# LoRasPi_02.net
KiCad netlist of a schematic drawn in Altium Designer
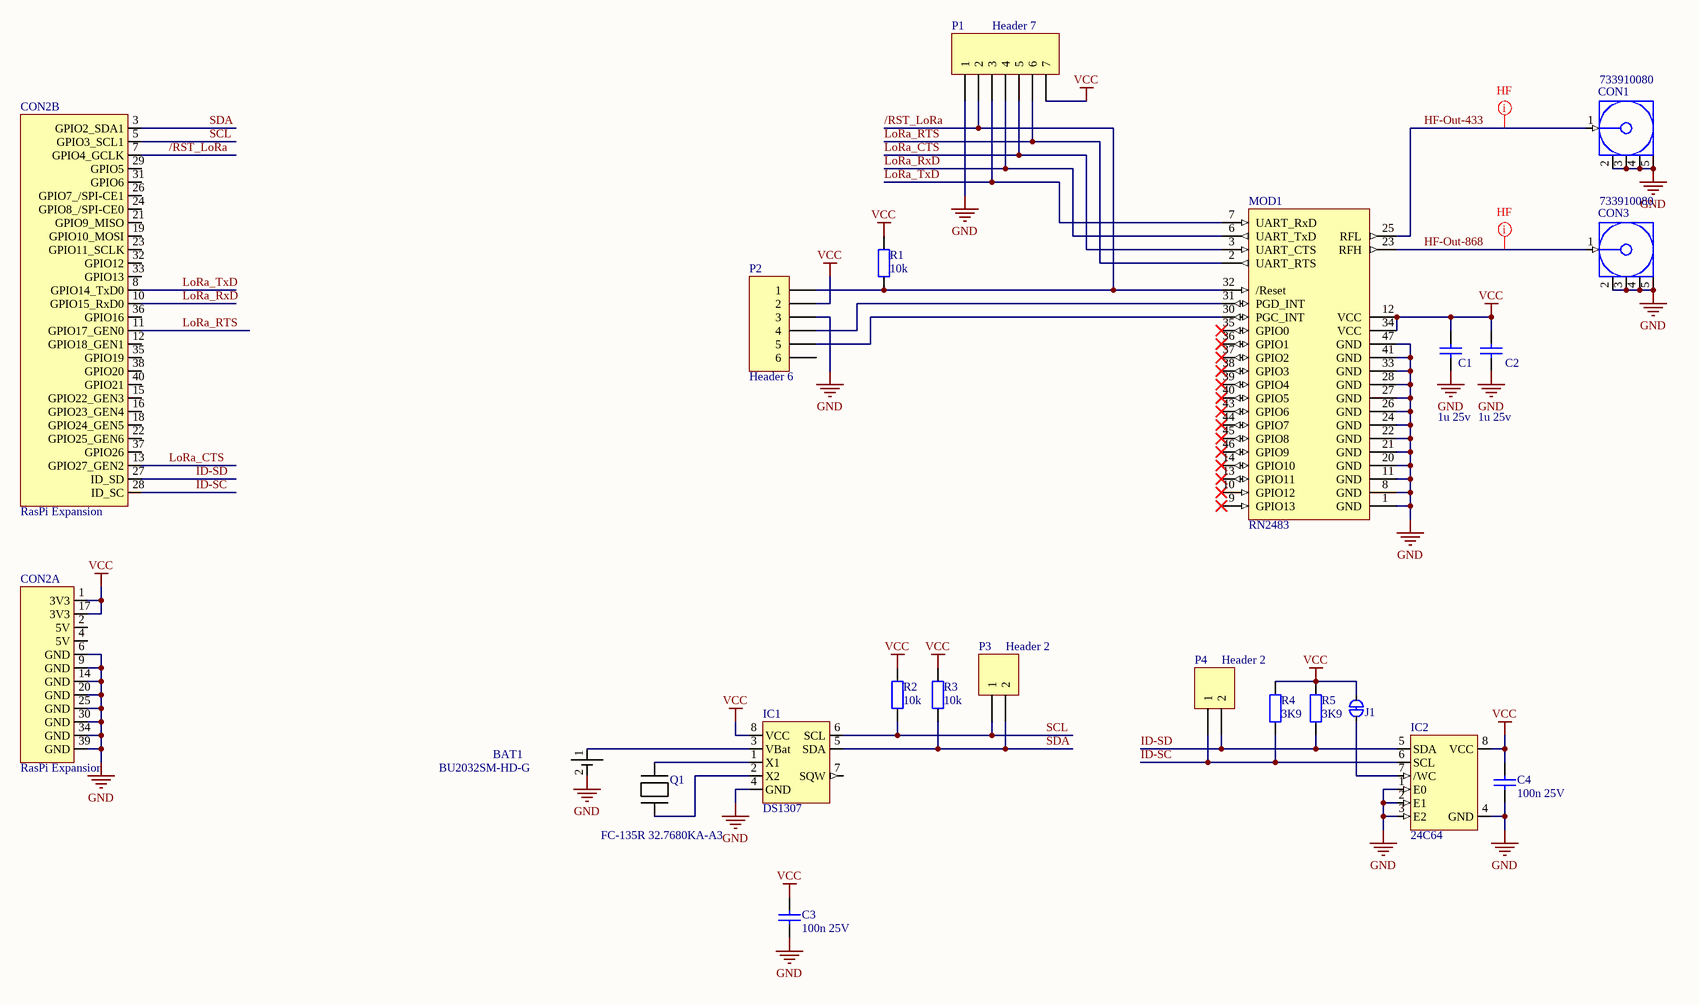
[diagram p0: LoRasPi_02.SchDoc]

(export (version "E")
  (design (tool "Eeschema 10.0.6"))
  (components
    (comp (ref "BAT1")
      (value "BU2032SM-HD-G")
      (footprint "BU2032SM-HD-G")
      (description "Batteriehalter CR2032")
      (libsource (lib "MyMisc") (part "BU2032SM-HD-G"))
    )
    (comp (ref "C1")
      (value "1u 25v")
      (footprint "C-0603-H")
      (description "Capacitor 1uF 25V")
      (libsource (lib "MyPASS") (part "C-0603-1u-25V"))
    )
    (comp (ref "C2")
      (value "1u 25v")
      (footprint "C-0603-H")
      (description "Capacitor 1uF 25V")
      (libsource (lib "MyPASS") (part "C-0603-1u-25V"))
    )
    (comp (ref "C3")
      (value "100n 25V")
      (footprint "C-0603-H")
      (description "Capacitor 100n 25V")
      (libsource (lib "MyPASS") (part "C-0603-100n-25V"))
    )
    (comp (ref "C4")
      (value "100n 25V")
      (footprint "C-0603-H")
      (description "Capacitor 100n 25V")
      (libsource (lib "MyPASS") (part "C-0603-100n-25V"))
    )
    (comp (ref "CON1")
      (value "733910080")
      (footprint "733910080")
      (description "SMA Connector THT gewinkelt")
      (libsource (lib "MyCONN") (part "733910080"))
    )
    (comp (ref "CON2")
      (value "RasPi Expansion")
      (footprint "RasPi Expansion")
      (description "Raspberry Pi, 40P Expansion port")
      (libsource (lib "MyCONN") (part "RasPi Expansion_2"))
    )
    (comp (ref "CON3")
      (value "733910080")
      (footprint "733910080")
      (description "SMA Connector THT gewinkelt")
      (libsource (lib "MyCONN") (part "733910080"))
    )
    (comp (ref "IC1")
      (value "DS1307")
      (footprint "SOIC8")
      (description "RTC, I2C, 64x8")
      (libsource (lib "MyMaxim") (part "DS1307"))
    )
    (comp (ref "IC2")
      (value "24C64")
      (footprint "TSSOP8")
      (description "EEPROM 64KBit I2C TSSOP8")
      (libsource (lib "MyST") (part "M24C64 DW"))
    )
    (comp (ref "J1")
      (value "Lötbrücke_kl")
      (footprint "Solderbridge_kl")
      (description "Lötbrücke klein")
      (libsource (lib "MyMisc") (part "Solderbridge_kl"))
    )
    (comp (ref "MOD1")
      (value "RN2483")
      (footprint "RN2483")
      (description "LoRa Modul")
      (libsource (lib "MyMicrochip") (part "RN2483"))
    )
    (comp (ref "P1")
      (value "Header 7")
      (footprint "HDR1X7")
      (description "Header, 7-Pin")
      (fields (field (name "PUBLISHER") "Altium Limited"))
      (libsource (lib "Miscellaneous Connectors") (part "Header 7"))
    )
    (comp (ref "P2")
      (value "Header 6")
      (footprint "HDR1X6")
      (description "Header, 6-Pin")
      (fields (field (name "PUBLISHER") "Altium Limited"))
      (libsource (lib "Miscellaneous Connectors") (part "Header 6"))
    )
    (comp (ref "P3")
      (value "Header 2")
      (footprint "HDR1X2")
      (description "Header, 2-Pin")
      (fields (field (name "PUBLISHER") "Altium Limited"))
      (libsource (lib "Miscellaneous Connectors") (part "Header 2"))
    )
    (comp (ref "P4")
      (value "Header 2")
      (footprint "HDR1X2")
      (description "Header, 2-Pin")
      (fields (field (name "PUBLISHER") "Altium Limited"))
      (libsource (lib "Miscellaneous Connectors") (part "Header 2"))
    )
    (comp (ref "Q1")
      (value "FC-135R 32.7680KA-A3")
      (footprint "FC-135")
      (description "32,768KHz")
      (libsource (lib "MyPASS") (part "Xtal FC-135 32.7680KA-A3"))
    )
    (comp (ref "R1")
      (value "10k")
      (footprint "R-0603-H")
      (description "Resistor 10k")
      (libsource (lib "MyPASS") (part "R-0603-10k"))
    )
    (comp (ref "R2")
      (value "10k")
      (footprint "R-0603-H")
      (description "Resistor 10k")
      (libsource (lib "MyPASS") (part "R-0603-10k"))
    )
    (comp (ref "R3")
      (value "10k")
      (footprint "R-0603-H")
      (description "Resistor 10k")
      (libsource (lib "MyPASS") (part "R-0603-10k"))
    )
    (comp (ref "R4")
      (value "3K9")
      (footprint "R-0603-M")
      (description "Resistor 3k9")
      (libsource (lib "MyPASS") (part "R-0603-3k9"))
    )
    (comp (ref "R5")
      (value "3K9")
      (footprint "R-0603-M")
      (description "Resistor 3k9")
      (libsource (lib "MyPASS") (part "R-0603-3k9"))
    )
  )
  (nets
    (net (code "1") (name "/HF-Out-433") (class "Default")
      (node (ref "CON1") (pin "1") (pinfunction "Signal_1") (pintype "input"))
      (node (ref "MOD1") (pin "25") (pinfunction "RFL_25") (pintype "output"))
    )
    (net (code "2") (name "/HF-Out-868") (class "Default")
      (node (ref "CON3") (pin "1") (pinfunction "Signal_1") (pintype "input"))
      (node (ref "MOD1") (pin "23") (pinfunction "RFH_23") (pintype "output"))
    )
    (net (code "3") (name "/ID-SC") (class "Default")
      (node (ref "CON2") (pin "28") (pinfunction "ID_SC_28") (pintype "bidirectional"))
      (node (ref "IC2") (pin "6") (pinfunction "SCL_6") (pintype "bidirectional"))
      (node (ref "P4") (pin "1") (pinfunction "1_1") (pintype "passive"))
      (node (ref "R4") (pin "1") (pinfunction "1_1") (pintype "passive"))
    )
    (net (code "4") (name "/ID-SD") (class "Default")
      (node (ref "CON2") (pin "27") (pinfunction "ID_SD_27") (pintype "bidirectional"))
      (node (ref "IC2") (pin "5") (pinfunction "SDA_5") (pintype "bidirectional"))
      (node (ref "P4") (pin "2") (pinfunction "2_2") (pintype "passive"))
      (node (ref "R5") (pin "1") (pinfunction "1_1") (pintype "passive"))
    )
    (net (code "5") (name "/LoRa_CTS") (class "Default")
      (node (ref "CON2") (pin "13") (pinfunction "GPIO27_GEN2_13") (pintype "bidirectional"))
      (node (ref "MOD1") (pin "3") (pinfunction "UART_CTS_3") (pintype "input"))
      (node (ref "P1") (pin "5") (pinfunction "5_5") (pintype "passive"))
    )
    (net (code "6") (name "/LoRa_RTS") (class "Default")
      (node (ref "CON2") (pin "11") (pinfunction "GPIO17_GEN0_11") (pintype "bidirectional"))
      (node (ref "MOD1") (pin "2") (pinfunction "UART_RTS_2") (pintype "output"))
      (node (ref "P1") (pin "6") (pinfunction "6_6") (pintype "passive"))
    )
    (net (code "7") (name "/LoRa_RxD") (class "Default")
      (node (ref "CON2") (pin "10") (pinfunction "GPIO15_RxD0_10") (pintype "bidirectional"))
      (node (ref "MOD1") (pin "6") (pinfunction "UART_TxD_6") (pintype "output"))
      (node (ref "P1") (pin "4") (pinfunction "4_4") (pintype "passive"))
    )
    (net (code "8") (name "/LoRa_TxD") (class "Default")
      (node (ref "CON2") (pin "8") (pinfunction "GPIO14_TxD0_8") (pintype "bidirectional"))
      (node (ref "MOD1") (pin "7") (pinfunction "UART_RxD_7") (pintype "input"))
      (node (ref "P1") (pin "3") (pinfunction "3_3") (pintype "passive"))
    )
    (net (code "9") (name "/SCL") (class "Default")
      (node (ref "CON2") (pin "5") (pinfunction "GPIO3_SCL1_5") (pintype "bidirectional"))
      (node (ref "IC1") (pin "6") (pinfunction "SCL_6") (pintype "bidirectional"))
      (node (ref "P3") (pin "1") (pinfunction "1_1") (pintype "passive"))
      (node (ref "R2") (pin "1") (pinfunction "1_1") (pintype "passive"))
    )
    (net (code "10") (name "/SDA") (class "Default")
      (node (ref "CON2") (pin "3") (pinfunction "GPIO2_SDA1_3") (pintype "bidirectional"))
      (node (ref "IC1") (pin "5") (pinfunction "SDA_5") (pintype "bidirectional"))
      (node (ref "P3") (pin "2") (pinfunction "2_2") (pintype "passive"))
      (node (ref "R3") (pin "1") (pinfunction "1_1") (pintype "passive"))
    )
    (net (code "11") (name "/{slash}RST_LoRa") (class "Default")
      (node (ref "CON2") (pin "7") (pinfunction "GPIO4_GCLK_7") (pintype "bidirectional"))
      (node (ref "MOD1") (pin "32") (pinfunction "/Reset_32") (pintype "input"))
      (node (ref "P1") (pin "2") (pinfunction "2_2") (pintype "passive"))
      (node (ref "P2") (pin "1") (pinfunction "1_1") (pintype "passive"))
      (node (ref "R1") (pin "1") (pinfunction "1_1") (pintype "passive"))
    )
    (net (code "12") (name "GND") (class "Default")
      (node (ref "BAT1") (pin "2") (pinfunction "-_2") (pintype "power_in"))
      (node (ref "C1") (pin "1") (pinfunction "1_1") (pintype "passive"))
      (node (ref "C2") (pin "1") (pinfunction "1_1") (pintype "passive"))
      (node (ref "C3") (pin "1") (pinfunction "1_1") (pintype "passive"))
      (node (ref "C4") (pin "1") (pinfunction "1_1") (pintype "passive"))
      (node (ref "CON1") (pin "2") (pinfunction "GND_2") (pintype "power_in"))
      (node (ref "CON1") (pin "3") (pinfunction "GND_3") (pintype "power_in"))
      (node (ref "CON1") (pin "4") (pinfunction "GND_4") (pintype "power_in"))
      (node (ref "CON1") (pin "5") (pinfunction "GND_5") (pintype "power_in"))
      (node (ref "CON2") (pin "14") (pinfunction "GND_14") (pintype "power_in"))
      (node (ref "CON2") (pin "20") (pinfunction "GND_20") (pintype "power_in"))
      (node (ref "CON2") (pin "25") (pinfunction "GND_25") (pintype "power_in"))
      (node (ref "CON2") (pin "30") (pinfunction "GND_30") (pintype "power_in"))
      (node (ref "CON2") (pin "34") (pinfunction "GND_34") (pintype "power_in"))
      (node (ref "CON2") (pin "39") (pinfunction "GND_39") (pintype "power_in"))
      (node (ref "CON2") (pin "6") (pinfunction "GND_6") (pintype "power_in"))
      (node (ref "CON2") (pin "9") (pinfunction "GND_9") (pintype "power_in"))
      (node (ref "CON3") (pin "2") (pinfunction "GND_2") (pintype "power_in"))
      (node (ref "CON3") (pin "3") (pinfunction "GND_3") (pintype "power_in"))
      (node (ref "CON3") (pin "4") (pinfunction "GND_4") (pintype "power_in"))
      (node (ref "CON3") (pin "5") (pinfunction "GND_5") (pintype "power_in"))
      (node (ref "IC1") (pin "4") (pinfunction "GND_4") (pintype "power_in"))
      (node (ref "IC2") (pin "1") (pinfunction "E0_1") (pintype "input"))
      (node (ref "IC2") (pin "2") (pinfunction "E1_2") (pintype "input"))
      (node (ref "IC2") (pin "3") (pinfunction "E2_3") (pintype "input"))
      (node (ref "IC2") (pin "4") (pinfunction "GND_4") (pintype "power_in"))
      (node (ref "MOD1") (pin "1") (pinfunction "GND_1") (pintype "power_in"))
      (node (ref "MOD1") (pin "11") (pinfunction "GND_11") (pintype "power_in"))
      (node (ref "MOD1") (pin "20") (pinfunction "GND_20") (pintype "power_in"))
      (node (ref "MOD1") (pin "21") (pinfunction "GND_21") (pintype "power_in"))
      (node (ref "MOD1") (pin "22") (pinfunction "GND_22") (pintype "power_in"))
      (node (ref "MOD1") (pin "24") (pinfunction "GND_24") (pintype "power_in"))
      (node (ref "MOD1") (pin "26") (pinfunction "GND_26") (pintype "power_in"))
      (node (ref "MOD1") (pin "27") (pinfunction "GND_27") (pintype "power_in"))
      (node (ref "MOD1") (pin "28") (pinfunction "GND_28") (pintype "power_in"))
      (node (ref "MOD1") (pin "33") (pinfunction "GND_33") (pintype "power_in"))
      (node (ref "MOD1") (pin "41") (pinfunction "GND_41") (pintype "power_in"))
      (node (ref "MOD1") (pin "47") (pinfunction "GND_47") (pintype "power_in"))
      (node (ref "MOD1") (pin "8") (pinfunction "GND_8") (pintype "power_in"))
      (node (ref "P1") (pin "1") (pinfunction "1_1") (pintype "passive"))
      (node (ref "P2") (pin "3") (pinfunction "3_3") (pintype "passive"))
    )
    (net (code "13") (name "Net-(BAT1-+)") (class "Default")
      (node (ref "BAT1") (pin "1") (pinfunction "+_1") (pintype "power_in"))
      (node (ref "IC1") (pin "3") (pinfunction "VBat_3") (pintype "power_in"))
    )
    (net (code "14") (name "Net-(IC1-X1)") (class "Default")
      (node (ref "IC1") (pin "1") (pinfunction "X1_1") (pintype "passive"))
      (node (ref "Q1") (pin "2") (pinfunction "2_2") (pintype "power_in"))
    )
    (net (code "15") (name "Net-(IC1-X2)") (class "Default")
      (node (ref "IC1") (pin "2") (pinfunction "X2_2") (pintype "passive"))
      (node (ref "Q1") (pin "1") (pinfunction "1_1") (pintype "power_in"))
    )
    (net (code "16") (name "Net-(IC2-{slash}WC)") (class "Default")
      (node (ref "IC2") (pin "7") (pinfunction "/WC_7") (pintype "input"))
      (node (ref "J1") (pin "2") (pinfunction "2_2") (pintype "passive"))
    )
    (net (code "17") (name "Net-(MOD1-PGC_INT)") (class "Default")
      (node (ref "MOD1") (pin "30") (pinfunction "PGC_INT_30") (pintype "bidirectional"))
      (node (ref "P2") (pin "5") (pinfunction "5_5") (pintype "passive"))
    )
    (net (code "18") (name "Net-(MOD1-PGD_INT)") (class "Default")
      (node (ref "MOD1") (pin "31") (pinfunction "PGD_INT_31") (pintype "bidirectional"))
      (node (ref "P2") (pin "4") (pinfunction "4_4") (pintype "passive"))
    )
    (net (code "19") (name "VCC") (class "Default")
      (node (ref "C1") (pin "2") (pinfunction "2_2") (pintype "passive"))
      (node (ref "C2") (pin "2") (pinfunction "2_2") (pintype "passive"))
      (node (ref "C3") (pin "2") (pinfunction "2_2") (pintype "passive"))
      (node (ref "C4") (pin "2") (pinfunction "2_2") (pintype "passive"))
      (node (ref "CON2") (pin "1") (pinfunction "3V3_1") (pintype "power_in"))
      (node (ref "CON2") (pin "17") (pinfunction "3V3_17") (pintype "power_in"))
      (node (ref "IC1") (pin "8") (pinfunction "VCC_8") (pintype "power_in"))
      (node (ref "IC2") (pin "8") (pinfunction "VCC_8") (pintype "power_in"))
      (node (ref "J1") (pin "1") (pinfunction "1_1") (pintype "passive"))
      (node (ref "MOD1") (pin "12") (pinfunction "VCC_12") (pintype "power_in"))
      (node (ref "MOD1") (pin "34") (pinfunction "VCC_34") (pintype "power_in"))
      (node (ref "P1") (pin "7") (pinfunction "7_7") (pintype "passive"))
      (node (ref "P2") (pin "2") (pinfunction "2_2") (pintype "passive"))
      (node (ref "R1") (pin "2") (pinfunction "2_2") (pintype "passive"))
      (node (ref "R2") (pin "2") (pinfunction "2_2") (pintype "passive"))
      (node (ref "R3") (pin "2") (pinfunction "2_2") (pintype "passive"))
      (node (ref "R4") (pin "2") (pinfunction "2_2") (pintype "passive"))
      (node (ref "R5") (pin "2") (pinfunction "2_2") (pintype "passive"))
    )
    (net (code "20") (name "unconnected-(CON2A-5V-Pad2)") (class "Default")
      (node (ref "CON2") (pin "2") (pinfunction "5V_2") (pintype "power_in"))
    )
    (net (code "21") (name "unconnected-(CON2A-5V-Pad4)") (class "Default")
      (node (ref "CON2") (pin "4") (pinfunction "5V_4") (pintype "power_in"))
    )
    (net (code "22") (name "unconnected-(CON2B-GPIO5-Pad29)") (class "Default")
      (node (ref "CON2") (pin "29") (pinfunction "GPIO5_29") (pintype "bidirectional"))
    )
    (net (code "23") (name "unconnected-(CON2B-GPIO6-Pad31)") (class "Default")
      (node (ref "CON2") (pin "31") (pinfunction "GPIO6_31") (pintype "bidirectional"))
    )
    (net (code "24") (name "unconnected-(CON2B-GPIO7_{slash}SPI-CE1-Pad26)") (class "Default")
      (node (ref "CON2") (pin "26") (pinfunction "GPIO7_/SPI-CE1_26") (pintype "bidirectional"))
    )
    (net (code "25") (name "unconnected-(CON2B-GPIO8_{slash}SPI-CE0-Pad24)") (class "Default")
      (node (ref "CON2") (pin "24") (pinfunction "GPIO8_/SPI-CE0_24") (pintype "bidirectional"))
    )
    (net (code "26") (name "unconnected-(CON2B-GPIO9_MISO-Pad21)") (class "Default")
      (node (ref "CON2") (pin "21") (pinfunction "GPIO9_MISO_21") (pintype "bidirectional"))
    )
    (net (code "27") (name "unconnected-(CON2B-GPIO10_MOSI-Pad19)") (class "Default")
      (node (ref "CON2") (pin "19") (pinfunction "GPIO10_MOSI_19") (pintype "bidirectional"))
    )
    (net (code "28") (name "unconnected-(CON2B-GPIO11_SCLK-Pad23)") (class "Default")
      (node (ref "CON2") (pin "23") (pinfunction "GPIO11_SCLK_23") (pintype "bidirectional"))
    )
    (net (code "29") (name "unconnected-(CON2B-GPIO12-Pad32)") (class "Default")
      (node (ref "CON2") (pin "32") (pinfunction "GPIO12_32") (pintype "bidirectional"))
    )
    (net (code "30") (name "unconnected-(CON2B-GPIO13-Pad33)") (class "Default")
      (node (ref "CON2") (pin "33") (pinfunction "GPIO13_33") (pintype "bidirectional"))
    )
    (net (code "31") (name "unconnected-(CON2B-GPIO16-Pad36)") (class "Default")
      (node (ref "CON2") (pin "36") (pinfunction "GPIO16_36") (pintype "bidirectional"))
    )
    (net (code "32") (name "unconnected-(CON2B-GPIO18_GEN1-Pad12)") (class "Default")
      (node (ref "CON2") (pin "12") (pinfunction "GPIO18_GEN1_12") (pintype "bidirectional"))
    )
    (net (code "33") (name "unconnected-(CON2B-GPIO19-Pad35)") (class "Default")
      (node (ref "CON2") (pin "35") (pinfunction "GPIO19_35") (pintype "bidirectional"))
    )
    (net (code "34") (name "unconnected-(CON2B-GPIO20-Pad38)") (class "Default")
      (node (ref "CON2") (pin "38") (pinfunction "GPIO20_38") (pintype "bidirectional"))
    )
    (net (code "35") (name "unconnected-(CON2B-GPIO21-Pad40)") (class "Default")
      (node (ref "CON2") (pin "40") (pinfunction "GPIO21_40") (pintype "bidirectional"))
    )
    (net (code "36") (name "unconnected-(CON2B-GPIO22_GEN3-Pad15)") (class "Default")
      (node (ref "CON2") (pin "15") (pinfunction "GPIO22_GEN3_15") (pintype "bidirectional"))
    )
    (net (code "37") (name "unconnected-(CON2B-GPIO23_GEN4-Pad16)") (class "Default")
      (node (ref "CON2") (pin "16") (pinfunction "GPIO23_GEN4_16") (pintype "bidirectional"))
    )
    (net (code "38") (name "unconnected-(CON2B-GPIO24_GEN5-Pad18)") (class "Default")
      (node (ref "CON2") (pin "18") (pinfunction "GPIO24_GEN5_18") (pintype "bidirectional"))
    )
    (net (code "39") (name "unconnected-(CON2B-GPIO25_GEN6-Pad22)") (class "Default")
      (node (ref "CON2") (pin "22") (pinfunction "GPIO25_GEN6_22") (pintype "bidirectional"))
    )
    (net (code "40") (name "unconnected-(CON2B-GPIO26-Pad37)") (class "Default")
      (node (ref "CON2") (pin "37") (pinfunction "GPIO26_37") (pintype "bidirectional"))
    )
    (net (code "41") (name "unconnected-(IC1-SQW-Pad7)") (class "Default")
      (node (ref "IC1") (pin "7") (pinfunction "SQW_7") (pintype "output"))
    )
    (net (code "42") (name "unconnected-(MOD1-GPIO0-Pad35)") (class "Default")
      (node (ref "MOD1") (pin "35") (pinfunction "GPIO0_35") (pintype "bidirectional+no_connect"))
    )
    (net (code "43") (name "unconnected-(MOD1-GPIO1-Pad36)") (class "Default")
      (node (ref "MOD1") (pin "36") (pinfunction "GPIO1_36") (pintype "bidirectional+no_connect"))
    )
    (net (code "44") (name "unconnected-(MOD1-GPIO2-Pad37)") (class "Default")
      (node (ref "MOD1") (pin "37") (pinfunction "GPIO2_37") (pintype "bidirectional+no_connect"))
    )
    (net (code "45") (name "unconnected-(MOD1-GPIO3-Pad38)") (class "Default")
      (node (ref "MOD1") (pin "38") (pinfunction "GPIO3_38") (pintype "bidirectional+no_connect"))
    )
    (net (code "46") (name "unconnected-(MOD1-GPIO4-Pad39)") (class "Default")
      (node (ref "MOD1") (pin "39") (pinfunction "GPIO4_39") (pintype "bidirectional+no_connect"))
    )
    (net (code "47") (name "unconnected-(MOD1-GPIO5-Pad40)") (class "Default")
      (node (ref "MOD1") (pin "40") (pinfunction "GPIO5_40") (pintype "bidirectional+no_connect"))
    )
    (net (code "48") (name "unconnected-(MOD1-GPIO6-Pad43)") (class "Default")
      (node (ref "MOD1") (pin "43") (pinfunction "GPIO6_43") (pintype "bidirectional+no_connect"))
    )
    (net (code "49") (name "unconnected-(MOD1-GPIO7-Pad44)") (class "Default")
      (node (ref "MOD1") (pin "44") (pinfunction "GPIO7_44") (pintype "bidirectional+no_connect"))
    )
    (net (code "50") (name "unconnected-(MOD1-GPIO8-Pad45)") (class "Default")
      (node (ref "MOD1") (pin "45") (pinfunction "GPIO8_45") (pintype "bidirectional+no_connect"))
    )
    (net (code "51") (name "unconnected-(MOD1-GPIO9-Pad46)") (class "Default")
      (node (ref "MOD1") (pin "46") (pinfunction "GPIO9_46") (pintype "bidirectional+no_connect"))
    )
    (net (code "52") (name "unconnected-(MOD1-GPIO10-Pad14)") (class "Default")
      (node (ref "MOD1") (pin "14") (pinfunction "GPIO10_14") (pintype "bidirectional+no_connect"))
    )
    (net (code "53") (name "unconnected-(MOD1-GPIO11-Pad13)") (class "Default")
      (node (ref "MOD1") (pin "13") (pinfunction "GPIO11_13") (pintype "bidirectional+no_connect"))
    )
    (net (code "54") (name "unconnected-(MOD1-GPIO12-Pad10)") (class "Default")
      (node (ref "MOD1") (pin "10") (pinfunction "GPIO12_10") (pintype "input+no_connect"))
    )
    (net (code "55") (name "unconnected-(MOD1-GPIO13-Pad9)") (class "Default")
      (node (ref "MOD1") (pin "9") (pinfunction "GPIO13_9") (pintype "input+no_connect"))
    )
    (net (code "56") (name "unconnected-(P2-Pad6)") (class "Default")
      (node (ref "P2") (pin "6") (pinfunction "6_6") (pintype "passive"))
    )
  )
)
